# Geiger_counter.net
KiCad netlist of a schematic drawn in EasyEDA
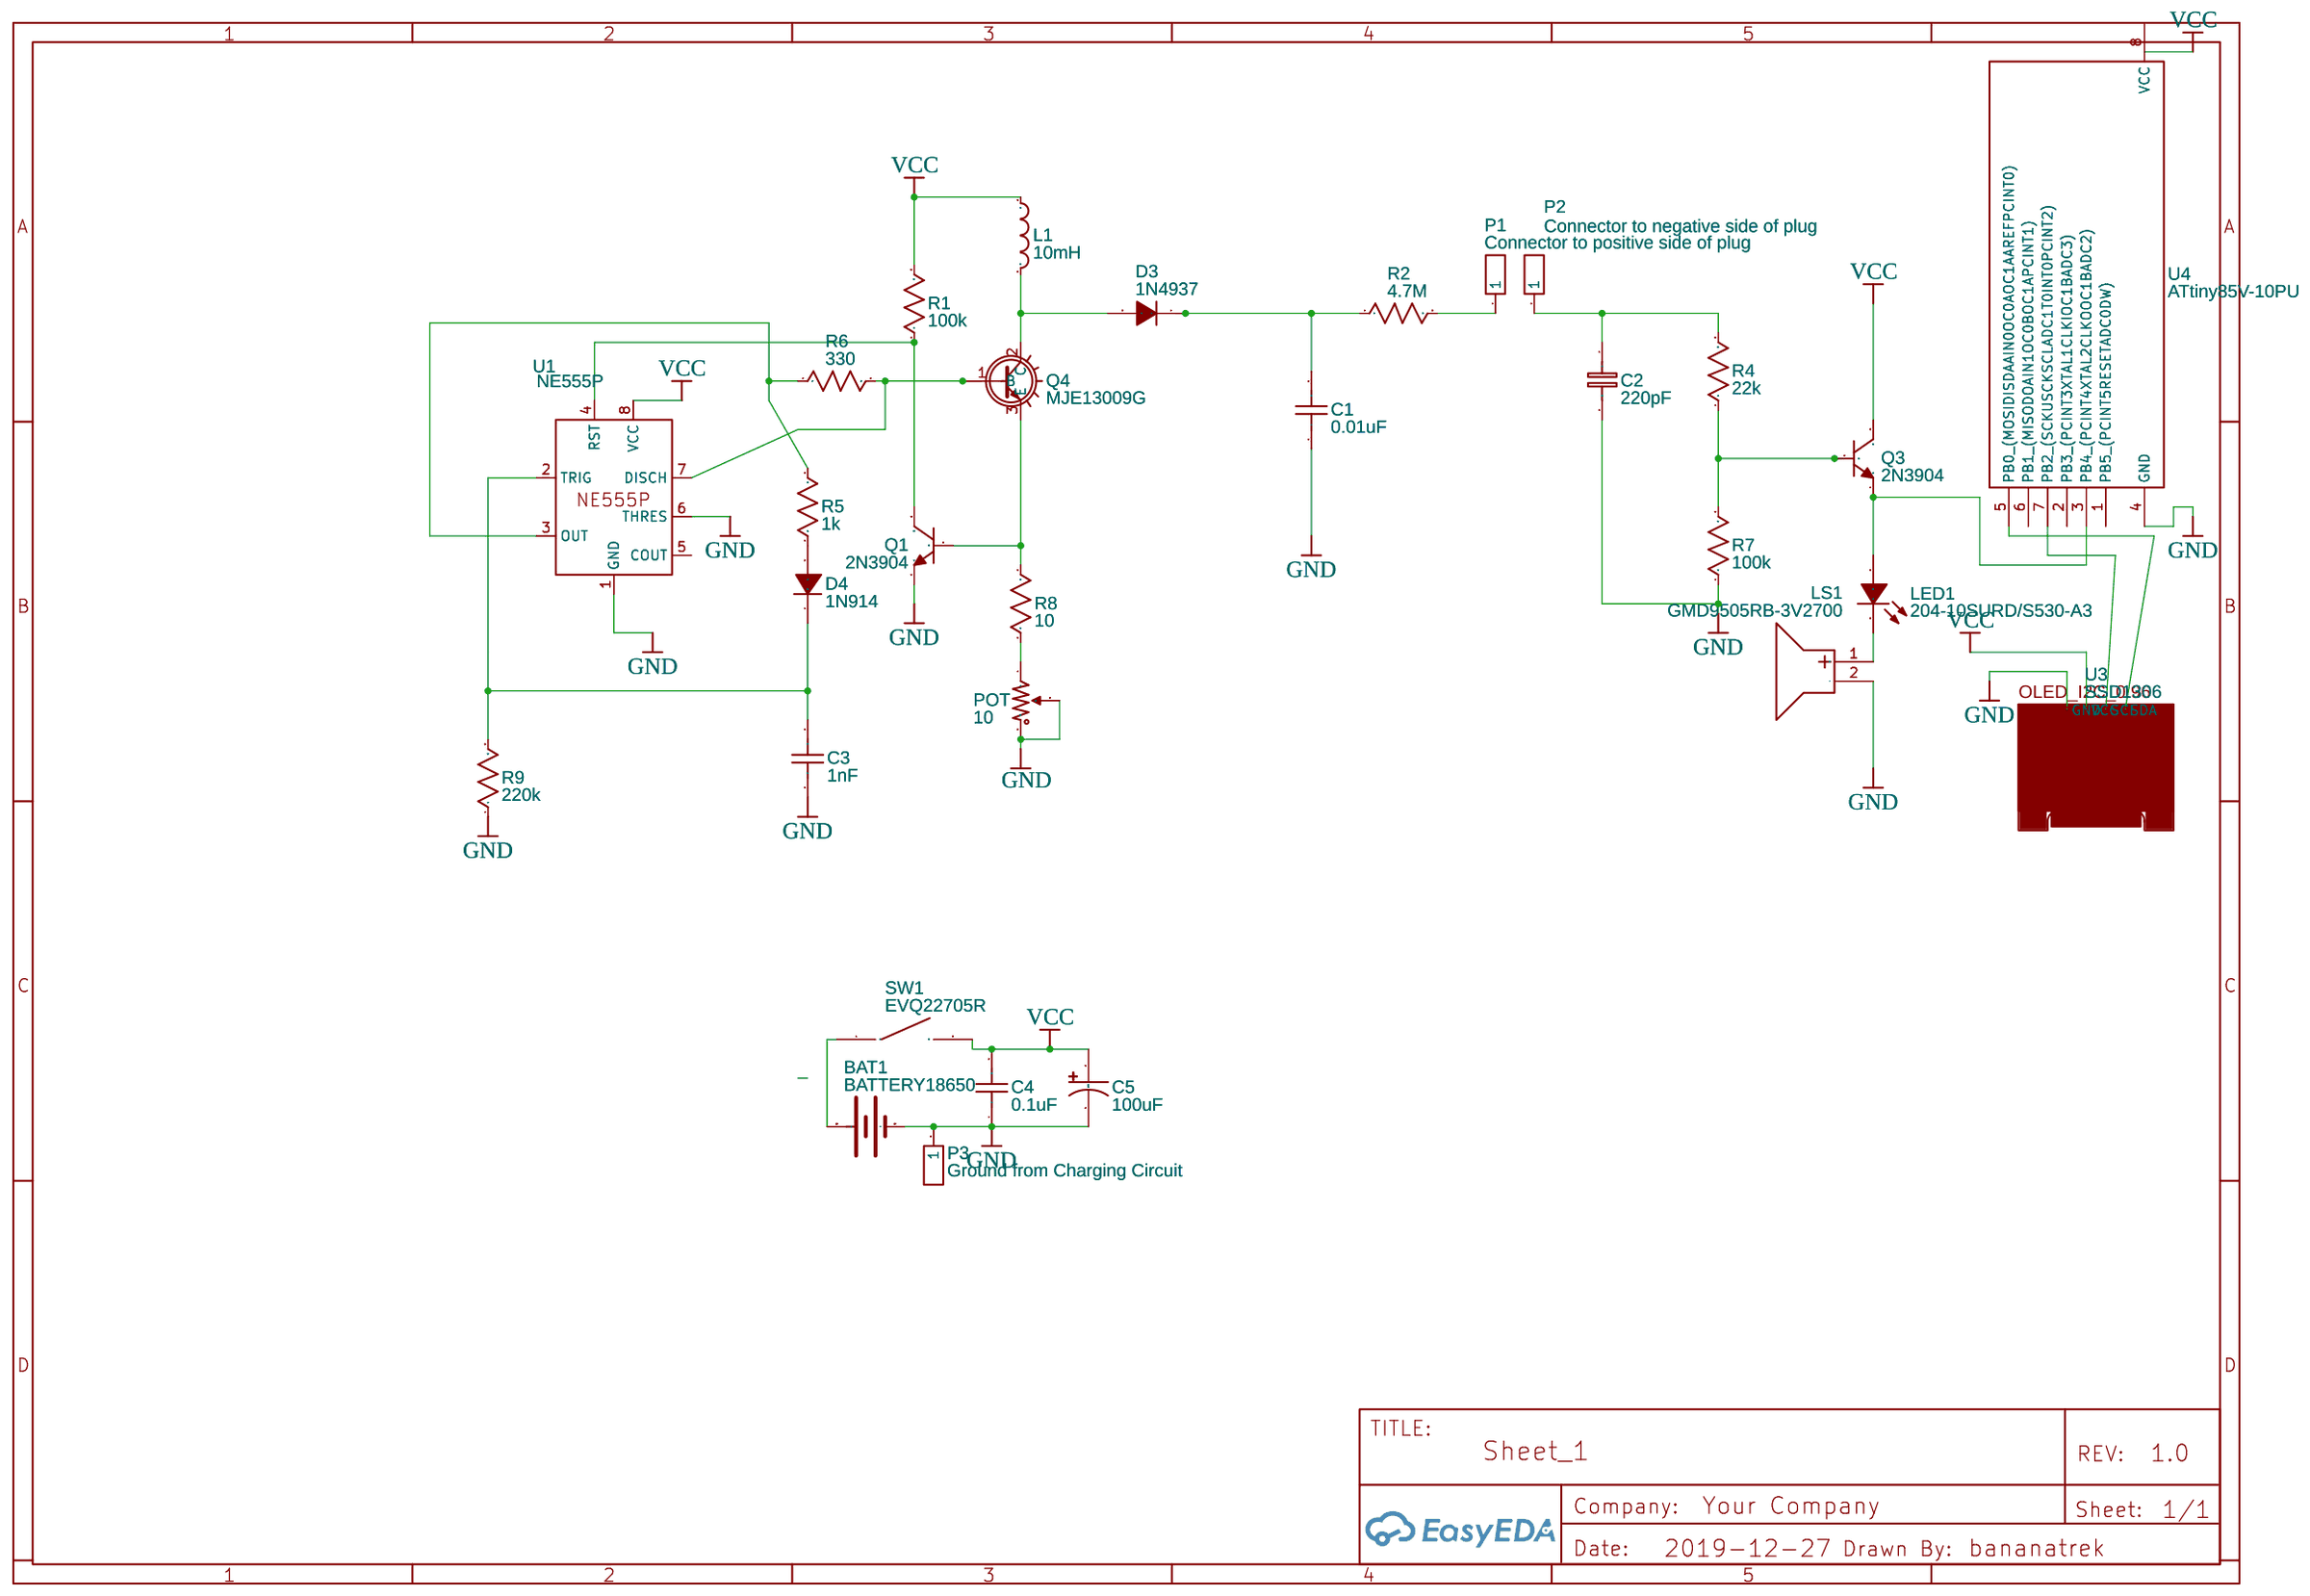
[diagram p0: schematic sheet]

(export (version "E")
  (design (tool "Eeschema 10.0.6"))
  (components
    (comp (ref "BAT1") (value "BATTERY18650") (libsource (lib "") (part "Unknown_440_570")))
    (comp (ref "C1") (value "0.01uF") (libsource (lib "") (part "Cap_RAD-0.1_US")))
    (comp (ref "C2") (value "220pF") (libsource (lib "") (part "Cap_RAD-0.1_EU")))
    (comp (ref "C3") (value "1nF") (libsource (lib "") (part "Cap_RAD-0.1_US")))
    (comp (ref "C4") (value "0.1uF") (libsource (lib "") (part "Cap_RAD-0.1_US")))
    (comp (ref "C5") (value "100uF") (libsource (lib "") (part "Cap_Electrolytic(TH)_D3.0XF1.5_US")))
    (comp (ref "D3")
      (value "1N4937")
      (fields (field (name "BOM_Supplier Part") "C237246"))
      (libsource (lib "") (part "Unknown_585_150"))
    )
    (comp (ref "D4")
      (value "1N914")
      (fields (field (name "BOM_Supplier Part") "C96325"))
      (libsource (lib "") (part "Unknown_410_290"))
    )
    (comp (ref "L1") (value "10mH") (libsource (lib "") (part "Inductor_AXIAL-0.4_US")))
    (comp (ref "LED1")
      (value "204-10SURD/S530-A3")
      (fields (field (name "BOM_Supplier Part") "C99772"))
      (libsource (lib "") (part "Unknown_965_295"))
    )
    (comp (ref "LS1")
      (value "GMD9505RB-3V2700")
      (fields (field (name "BOM_Supplier Part") "C252935"))
      (libsource (lib "") (part "Unknown_940_340"))
    )
    (comp (ref "P1")
      (value "Connector to positive side of plug")
      (fields
        (field (name "BOM_Manufacturer Part") "Header-Male-2.54_1x1")
        (field (name "BOM_Supplier Part") "C81276")
      )
      (libsource (lib "") (part "Unknown_765_135"))
    )
    (comp (ref "P2")
      (value "Connector to negative side of plug")
      (fields
        (field (name "BOM_Manufacturer Part") "Header-Male-2.54_1x1")
        (field (name "BOM_Supplier Part") "C81276")
      )
      (libsource (lib "") (part "Unknown_785_135"))
    )
    (comp (ref "P3")
      (value "Ground from Charging Circuit")
      (fields
        (field (name "BOM_Manufacturer Part") "Header-Male-2.54_1x1")
        (field (name "BOM_Supplier Part") "C81276")
      )
      (libsource (lib "") (part "Unknown_475_585"))
    )
    (comp (ref "POT") (value "10") (libsource (lib "") (part "Potentiometer")))
    (comp (ref "Q1")
      (value "2N3904")
      (fields (field (name "BOM_Supplier Part") "C118538"))
      (libsource (lib "") (part "Unknown_475_270"))
    )
    (comp (ref "Q3")
      (value "2N3904")
      (fields (field (name "BOM_Supplier Part") "C118538"))
      (libsource (lib "") (part "Unknown_950_225"))
    )
    (comp (ref "Q4") (value "MJE13009G") (libsource (lib "") (part "Unknown_510_185")))
    (comp (ref "R1") (value "100k") (libsource (lib "") (part "Res_AXIAL-0.3(1/8W)_US_1")))
    (comp (ref "R2") (value "4.7M") (libsource (lib "") (part "Res_AXIAL-0.3(1/8W)_US")))
    (comp (ref "R4") (value "22k") (libsource (lib "") (part "Res_AXIAL-0.3(1/8W)_US_1")))
    (comp (ref "R5") (value "1k") (libsource (lib "") (part "Res_AXIAL-0.3(1/8W)_US_1")))
    (comp (ref "R6") (value "330") (libsource (lib "") (part "Res_AXIAL-0.3(1/8W)_US")))
    (comp (ref "R7") (value "100k") (libsource (lib "") (part "Res_AXIAL-0.3(1/8W)_US_1")))
    (comp (ref "R8") (value "10") (libsource (lib "") (part "Res_AXIAL-0.3(1/8W)_US_1")))
    (comp (ref "R9") (value "220k") (libsource (lib "") (part "Res_AXIAL-0.3(1/8W)_US_1")))
    (comp (ref "SW1")
      (value "EVQ22705R")
      (fields (field (name "BOM_Supplier Part") "C79156"))
      (libsource (lib "") (part "Unknown_460_525"))
    )
    (comp (ref "U1")
      (value "NE555P")
      (fields (field (name "BOM_Supplier Part") "C46749"))
      (libsource (lib "") (part "Unknown_310_245"))
    )
    (comp (ref "U3") (value "SSD1306") (libsource (lib "") (part "Unknown_1080_385")))
    (comp (ref "U4") (value "ATtiny85V-10PU") (libsource (lib "") (part "Unknown_1065_130")))
  )
  (nets
    (net (code "1") (name "GND") (class "Default")
      (node (ref "BAT1") (pin "GND@1") (pinfunction "-_GND@1") (pintype "passive"))
      (node (ref "C1") (pin "1") (pinfunction "1_1") (pintype "unspecified"))
      (node (ref "C2") (pin "2") (pinfunction "2_2") (pintype "unspecified"))
      (node (ref "C3") (pin "1") (pinfunction "1_1") (pintype "unspecified"))
      (node (ref "C4") (pin "1") (pinfunction "1_1") (pintype "unspecified"))
      (node (ref "C5") (pin "2") (pinfunction "2_2") (pintype "unspecified"))
      (node (ref "LS1") (pin "2") (pinfunction "-_2") (pintype "unspecified"))
      (node (ref "P3") (pin "1") (pinfunction "1_1") (pintype "input"))
      (node (ref "POT") (pin "2") (pinfunction "3_2") (pintype "unspecified"))
      (node (ref "POT") (pin "3") (pinfunction "2_3") (pintype "unspecified"))
      (node (ref "Q1") (pin "1") (pinfunction "E_1") (pintype "unspecified"))
      (node (ref "R7") (pin "1") (pinfunction "1_1") (pintype "unspecified"))
      (node (ref "R9") (pin "1") (pinfunction "1_1") (pintype "unspecified"))
      (node (ref "U1") (pin "1") (pinfunction "GND_1") (pintype "unspecified"))
      (node (ref "U1") (pin "6") (pinfunction "THRES_6") (pintype "unspecified"))
      (node (ref "U3") (pin "1") (pinfunction "GND_1") (pintype "unspecified"))
      (node (ref "U4") (pin "4") (pinfunction "GND_4") (pintype "passive"))
    )
    (net (code "2") (name "Net-(BAT1-+)") (class "Default")
      (node (ref "BAT1") (pin "PWR@1") (pinfunction "+_PWR@1") (pintype "passive"))
      (node (ref "SW1") (pin "1") (pinfunction "1_1") (pintype "input"))
    )
    (net (code "3") (name "Net-(C2-Pad1)") (class "Default")
      (node (ref "C2") (pin "1") (pinfunction "1_1") (pintype "unspecified"))
      (node (ref "P2") (pin "1") (pinfunction "1_1") (pintype "input"))
      (node (ref "R4") (pin "2") (pinfunction "2_2") (pintype "unspecified"))
    )
    (net (code "4") (name "Net-(D3-A)") (class "Default")
      (node (ref "D3") (pin "2") (pinfunction "A_2") (pintype "unspecified"))
      (node (ref "L1") (pin "2") (pinfunction "2_2") (pintype "unspecified"))
      (node (ref "Q4") (pin "2") (pinfunction "C_2") (pintype "unspecified"))
    )
    (net (code "5") (name "Net-(D3-K)") (class "Default")
      (node (ref "C1") (pin "2") (pinfunction "2_2") (pintype "unspecified"))
      (node (ref "D3") (pin "1") (pinfunction "K_1") (pintype "unspecified"))
      (node (ref "R2") (pin "1") (pinfunction "1_1") (pintype "unspecified"))
    )
    (net (code "6") (name "Net-(D4-A)") (class "Default")
      (node (ref "D4") (pin "2") (pinfunction "A_2") (pintype "unspecified"))
      (node (ref "R5") (pin "1") (pinfunction "1_1") (pintype "unspecified"))
    )
    (net (code "7") (name "Net-(D4-K)") (class "Default")
      (node (ref "C3") (pin "2") (pinfunction "2_2") (pintype "unspecified"))
      (node (ref "D4") (pin "1") (pinfunction "K_1") (pintype "unspecified"))
      (node (ref "R9") (pin "2") (pinfunction "2_2") (pintype "unspecified"))
      (node (ref "U1") (pin "2") (pinfunction "TRIG_2") (pintype "unspecified"))
    )
    (net (code "8") (name "Net-(LED1-A)") (class "Default")
      (node (ref "LED1") (pin "1") (pinfunction "A_1") (pintype "unspecified"))
      (node (ref "Q3") (pin "1") (pinfunction "E_1") (pintype "unspecified"))
      (node (ref "U4") (pin "3") (pinfunction "PB4_(PCINT4XTAL2CLKOOC1BADC2)_3") (pintype "bidirectional"))
    )
    (net (code "9") (name "Net-(LED1-K)") (class "Default")
      (node (ref "LED1") (pin "2") (pinfunction "K_2") (pintype "unspecified"))
      (node (ref "LS1") (pin "1") (pinfunction "+_1") (pintype "unspecified"))
    )
    (net (code "10") (name "Net-(P1-Pad1)") (class "Default")
      (node (ref "P1") (pin "1") (pinfunction "1_1") (pintype "input"))
      (node (ref "R2") (pin "2") (pinfunction "2_2") (pintype "unspecified"))
    )
    (net (code "11") (name "Net-(POT-Pad1)") (class "Default")
      (node (ref "POT") (pin "1") (pinfunction "1_1") (pintype "unspecified"))
      (node (ref "R8") (pin "1") (pinfunction "1_1") (pintype "unspecified"))
    )
    (net (code "12") (name "Net-(Q1-B)") (class "Default")
      (node (ref "Q1") (pin "2") (pinfunction "B_2") (pintype "unspecified"))
      (node (ref "Q4") (pin "3") (pinfunction "E_3") (pintype "unspecified"))
      (node (ref "R8") (pin "2") (pinfunction "2_2") (pintype "unspecified"))
    )
    (net (code "13") (name "Net-(Q1-C)") (class "Default")
      (node (ref "Q1") (pin "3") (pinfunction "C_3") (pintype "unspecified"))
      (node (ref "R1") (pin "1") (pinfunction "1_1") (pintype "unspecified"))
      (node (ref "U1") (pin "4") (pinfunction "RST_4") (pintype "unspecified"))
    )
    (net (code "14") (name "Net-(Q3-B)") (class "Default")
      (node (ref "Q3") (pin "2") (pinfunction "B_2") (pintype "unspecified"))
      (node (ref "R4") (pin "1") (pinfunction "1_1") (pintype "unspecified"))
      (node (ref "R7") (pin "2") (pinfunction "2_2") (pintype "unspecified"))
    )
    (net (code "15") (name "Net-(Q4-B)") (class "Default")
      (node (ref "Q4") (pin "1") (pinfunction "B_1") (pintype "input"))
      (node (ref "R6") (pin "2") (pinfunction "2_2") (pintype "unspecified"))
      (node (ref "U1") (pin "7") (pinfunction "DISCH_7") (pintype "unspecified"))
    )
    (net (code "16") (name "Net-(U1-OUT)") (class "Default")
      (node (ref "R5") (pin "2") (pinfunction "2_2") (pintype "unspecified"))
      (node (ref "R6") (pin "1") (pinfunction "1_1") (pintype "unspecified"))
      (node (ref "U1") (pin "3") (pinfunction "OUT_3") (pintype "unspecified"))
    )
    (net (code "17") (name "Net-(U3-SCL)") (class "Default")
      (node (ref "U3") (pin "4") (pinfunction "SCL_4") (pintype "unspecified"))
      (node (ref "U4") (pin "7") (pinfunction "PB2_(SCKUSCKSCLADC1T0INT0PCINT2)_7") (pintype "bidirectional"))
    )
    (net (code "18") (name "Net-(U3-SDA)") (class "Default")
      (node (ref "U3") (pin "3") (pinfunction "SDA_3") (pintype "unspecified"))
      (node (ref "U4") (pin "5") (pinfunction "PB0_(MOSIDISDAAIN0OC0AOC1AAREFPCINT0)_5") (pintype "bidirectional"))
    )
    (net (code "19") (name "VCC") (class "Default")
      (node (ref "C4") (pin "2") (pinfunction "2_2") (pintype "unspecified"))
      (node (ref "C5") (pin "1") (pinfunction "1_1") (pintype "unspecified"))
      (node (ref "L1") (pin "1") (pinfunction "1_1") (pintype "unspecified"))
      (node (ref "Q3") (pin "3") (pinfunction "C_3") (pintype "unspecified"))
      (node (ref "R1") (pin "2") (pinfunction "2_2") (pintype "unspecified"))
      (node (ref "SW1") (pin "2") (pinfunction "2_2") (pintype "input"))
      (node (ref "U1") (pin "8") (pinfunction "VCC_8") (pintype "unspecified"))
      (node (ref "U3") (pin "2") (pinfunction "VCC_2") (pintype "unspecified"))
    )
    (net (code "20") (name "unconnected-(U1-COUT-Pad5)") (class "Default")
      (node (ref "U1") (pin "5") (pinfunction "COUT_5") (pintype "unspecified"))
    )
    (net (code "21") (name "unconnected-(U4-PB1_(MISODOAIN1OC0BOC1APCINT1)-Pad6)") (class "Default")
      (node (ref "U4") (pin "6") (pinfunction "PB1_(MISODOAIN1OC0BOC1APCINT1)_6") (pintype "bidirectional"))
    )
    (net (code "22") (name "unconnected-(U4-PB3_(PCINT3XTAL1CLKIOC1BADC3)-Pad2)") (class "Default")
      (node (ref "U4") (pin "2") (pinfunction "PB3_(PCINT3XTAL1CLKIOC1BADC3)_2") (pintype "bidirectional"))
    )
    (net (code "23") (name "unconnected-(U4-PB5_(PCINT5RESETADC0DW)-Pad1)") (class "Default")
      (node (ref "U4") (pin "1") (pinfunction "PB5_(PCINT5RESETADC0DW)_1") (pintype "bidirectional"))
    )
    (net (code "24") (name "unconnected-(U4-VCC-Pad8)") (class "Default")
      (node (ref "U4") (pin "8") (pinfunction "VCC_8") (pintype "passive"))
    )
  )
)
